# Omnetics.net
KiCad netlist of a schematic drawn in Altium Designer
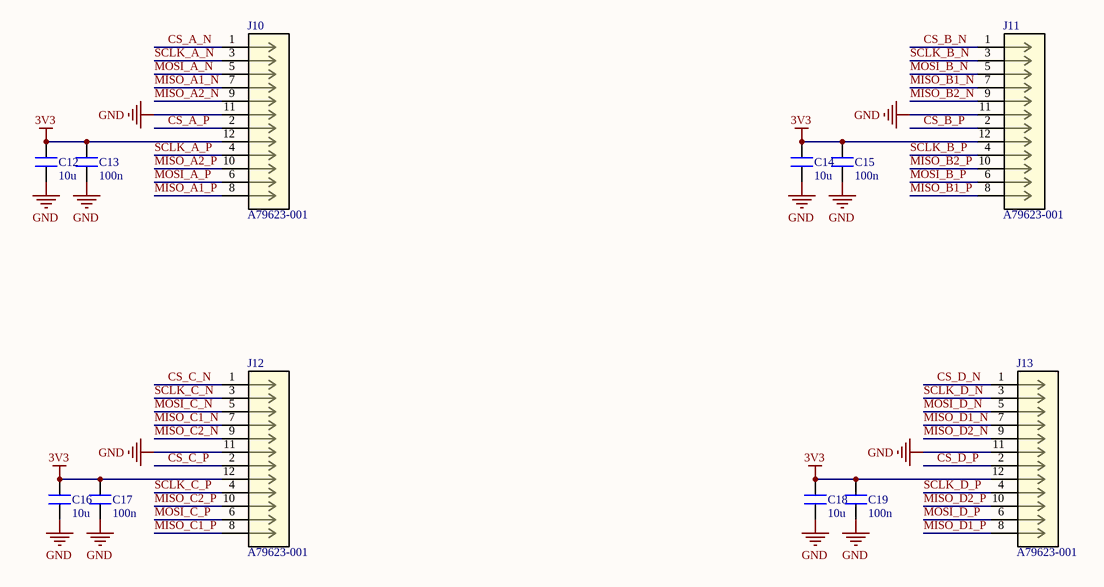
[diagram p0: Omnetics.SchDoc]

(export (version "E")
  (design (tool "Eeschema 10.0.6"))
  (components
    (comp (ref "C12") (value "10u") (footprint "C 0603_L") (libsource (lib "ZYNQ_开发板") (part "C_1_8")))
    (comp (ref "C13") (value "100n") (footprint "C 0402_L") (libsource (lib "ZYNQ_开发板") (part "C_1")))
    (comp (ref "C14") (value "10u") (footprint "C 0603_L") (libsource (lib "ZYNQ_开发板") (part "C_1_8")))
    (comp (ref "C15") (value "100n") (footprint "C 0402_L") (libsource (lib "ZYNQ_开发板") (part "C_1")))
    (comp (ref "C16") (value "10u") (footprint "C 0603_L") (libsource (lib "ZYNQ_开发板") (part "C_1_8")))
    (comp (ref "C17") (value "100n") (footprint "C 0402_L") (libsource (lib "ZYNQ_开发板") (part "C_1")))
    (comp (ref "C18") (value "10u") (footprint "C 0603_L") (libsource (lib "ZYNQ_开发板") (part "C_1_8")))
    (comp (ref "C19") (value "100n") (footprint "C 0402_L") (libsource (lib "ZYNQ_开发板") (part "C_1")))
    (comp (ref "J10")
      (value "A79623-001")
      (footprint "CONN_A79623-001_OMN")
      (description "Description")
      (fields (field (name "COPYRIGHT") "Copyright (C) 2026 Ultra Librarian. All rights reserved."))
      (libsource (lib "A79623-001") (part "A79623-001"))
    )
    (comp (ref "J11")
      (value "A79623-001")
      (footprint "CONN_A79623-001_OMN")
      (description "Description")
      (fields (field (name "COPYRIGHT") "Copyright (C) 2026 Ultra Librarian. All rights reserved."))
      (libsource (lib "A79623-001") (part "A79623-001"))
    )
    (comp (ref "J12")
      (value "A79623-001")
      (footprint "CONN_A79623-001_OMN")
      (description "Description")
      (fields (field (name "COPYRIGHT") "Copyright (C) 2026 Ultra Librarian. All rights reserved."))
      (libsource (lib "A79623-001") (part "A79623-001"))
    )
    (comp (ref "J13")
      (value "A79623-001")
      (footprint "CONN_A79623-001_OMN")
      (description "Description")
      (fields (field (name "COPYRIGHT") "Copyright (C) 2026 Ultra Librarian. All rights reserved."))
      (libsource (lib "A79623-001") (part "A79623-001"))
    )
  )
  (nets
    (net (code "1") (name "/CS_A_N") (class "Default")
      (node (ref "J10") (pin "1") (pinfunction "1_1") (pintype "passive"))
    )
    (net (code "2") (name "/CS_A_P") (class "Default")
      (node (ref "J10") (pin "2") (pinfunction "2_2") (pintype "passive"))
    )
    (net (code "3") (name "/CS_B_N") (class "Default")
      (node (ref "J11") (pin "1") (pinfunction "1_1") (pintype "passive"))
    )
    (net (code "4") (name "/CS_B_P") (class "Default")
      (node (ref "J11") (pin "2") (pinfunction "2_2") (pintype "passive"))
    )
    (net (code "5") (name "/CS_C_N") (class "Default")
      (node (ref "J12") (pin "1") (pinfunction "1_1") (pintype "passive"))
    )
    (net (code "6") (name "/CS_C_P") (class "Default")
      (node (ref "J12") (pin "2") (pinfunction "2_2") (pintype "passive"))
    )
    (net (code "7") (name "/CS_D_N") (class "Default")
      (node (ref "J13") (pin "1") (pinfunction "1_1") (pintype "passive"))
    )
    (net (code "8") (name "/CS_D_P") (class "Default")
      (node (ref "J13") (pin "2") (pinfunction "2_2") (pintype "passive"))
    )
    (net (code "9") (name "/MISO_A1_N") (class "Default")
      (node (ref "J10") (pin "7") (pinfunction "7_7") (pintype "passive"))
    )
    (net (code "10") (name "/MISO_A1_P") (class "Default")
      (node (ref "J10") (pin "8") (pinfunction "8_8") (pintype "passive"))
    )
    (net (code "11") (name "/MISO_A2_N") (class "Default")
      (node (ref "J10") (pin "9") (pinfunction "9_9") (pintype "passive"))
    )
    (net (code "12") (name "/MISO_A2_P") (class "Default")
      (node (ref "J10") (pin "10") (pinfunction "10_10") (pintype "passive"))
    )
    (net (code "13") (name "/MISO_B1_N") (class "Default")
      (node (ref "J11") (pin "7") (pinfunction "7_7") (pintype "passive"))
    )
    (net (code "14") (name "/MISO_B1_P") (class "Default")
      (node (ref "J11") (pin "8") (pinfunction "8_8") (pintype "passive"))
    )
    (net (code "15") (name "/MISO_B2_N") (class "Default")
      (node (ref "J11") (pin "9") (pinfunction "9_9") (pintype "passive"))
    )
    (net (code "16") (name "/MISO_B2_P") (class "Default")
      (node (ref "J11") (pin "10") (pinfunction "10_10") (pintype "passive"))
    )
    (net (code "17") (name "/MISO_C1_N") (class "Default")
      (node (ref "J12") (pin "7") (pinfunction "7_7") (pintype "passive"))
    )
    (net (code "18") (name "/MISO_C1_P") (class "Default")
      (node (ref "J12") (pin "8") (pinfunction "8_8") (pintype "passive"))
    )
    (net (code "19") (name "/MISO_C2_N") (class "Default")
      (node (ref "J12") (pin "9") (pinfunction "9_9") (pintype "passive"))
    )
    (net (code "20") (name "/MISO_C2_P") (class "Default")
      (node (ref "J12") (pin "10") (pinfunction "10_10") (pintype "passive"))
    )
    (net (code "21") (name "/MISO_D1_N") (class "Default")
      (node (ref "J13") (pin "7") (pinfunction "7_7") (pintype "passive"))
    )
    (net (code "22") (name "/MISO_D1_P") (class "Default")
      (node (ref "J13") (pin "8") (pinfunction "8_8") (pintype "passive"))
    )
    (net (code "23") (name "/MISO_D2_N") (class "Default")
      (node (ref "J13") (pin "9") (pinfunction "9_9") (pintype "passive"))
    )
    (net (code "24") (name "/MISO_D2_P") (class "Default")
      (node (ref "J13") (pin "10") (pinfunction "10_10") (pintype "passive"))
    )
    (net (code "25") (name "/MOSI_A_N") (class "Default")
      (node (ref "J10") (pin "5") (pinfunction "5_5") (pintype "passive"))
    )
    (net (code "26") (name "/MOSI_A_P") (class "Default")
      (node (ref "J10") (pin "6") (pinfunction "6_6") (pintype "passive"))
    )
    (net (code "27") (name "/MOSI_B_N") (class "Default")
      (node (ref "J11") (pin "5") (pinfunction "5_5") (pintype "passive"))
    )
    (net (code "28") (name "/MOSI_B_P") (class "Default")
      (node (ref "J11") (pin "6") (pinfunction "6_6") (pintype "passive"))
    )
    (net (code "29") (name "/MOSI_C_N") (class "Default")
      (node (ref "J12") (pin "5") (pinfunction "5_5") (pintype "passive"))
    )
    (net (code "30") (name "/MOSI_C_P") (class "Default")
      (node (ref "J12") (pin "6") (pinfunction "6_6") (pintype "passive"))
    )
    (net (code "31") (name "/MOSI_D_N") (class "Default")
      (node (ref "J13") (pin "5") (pinfunction "5_5") (pintype "passive"))
    )
    (net (code "32") (name "/MOSI_D_P") (class "Default")
      (node (ref "J13") (pin "6") (pinfunction "6_6") (pintype "passive"))
    )
    (net (code "33") (name "/SCLK_A_N") (class "Default")
      (node (ref "J10") (pin "3") (pinfunction "3_3") (pintype "passive"))
    )
    (net (code "34") (name "/SCLK_A_P") (class "Default")
      (node (ref "J10") (pin "4") (pinfunction "4_4") (pintype "passive"))
    )
    (net (code "35") (name "/SCLK_B_N") (class "Default")
      (node (ref "J11") (pin "3") (pinfunction "3_3") (pintype "passive"))
    )
    (net (code "36") (name "/SCLK_B_P") (class "Default")
      (node (ref "J11") (pin "4") (pinfunction "4_4") (pintype "passive"))
    )
    (net (code "37") (name "/SCLK_C_N") (class "Default")
      (node (ref "J12") (pin "3") (pinfunction "3_3") (pintype "passive"))
    )
    (net (code "38") (name "/SCLK_C_P") (class "Default")
      (node (ref "J12") (pin "4") (pinfunction "4_4") (pintype "passive"))
    )
    (net (code "39") (name "/SCLK_D_N") (class "Default")
      (node (ref "J13") (pin "3") (pinfunction "3_3") (pintype "passive"))
    )
    (net (code "40") (name "/SCLK_D_P") (class "Default")
      (node (ref "J13") (pin "4") (pinfunction "4_4") (pintype "passive"))
    )
    (net (code "41") (name "3V3") (class "Default")
      (node (ref "C12") (pin "2") (pintype "passive"))
      (node (ref "C13") (pin "2") (pintype "passive"))
      (node (ref "C14") (pin "2") (pintype "passive"))
      (node (ref "C15") (pin "2") (pintype "passive"))
      (node (ref "C16") (pin "2") (pintype "passive"))
      (node (ref "C17") (pin "2") (pintype "passive"))
      (node (ref "C18") (pin "2") (pintype "passive"))
      (node (ref "C19") (pin "2") (pintype "passive"))
      (node (ref "J10") (pin "12") (pinfunction "12_12") (pintype "passive"))
      (node (ref "J11") (pin "12") (pinfunction "12_12") (pintype "passive"))
      (node (ref "J12") (pin "12") (pinfunction "12_12") (pintype "passive"))
      (node (ref "J13") (pin "12") (pinfunction "12_12") (pintype "passive"))
    )
    (net (code "42") (name "GND") (class "Default")
      (node (ref "C12") (pin "1") (pintype "passive"))
      (node (ref "C13") (pin "1") (pintype "passive"))
      (node (ref "C14") (pin "1") (pintype "passive"))
      (node (ref "C15") (pin "1") (pintype "passive"))
      (node (ref "C16") (pin "1") (pintype "passive"))
      (node (ref "C17") (pin "1") (pintype "passive"))
      (node (ref "C18") (pin "1") (pintype "passive"))
      (node (ref "C19") (pin "1") (pintype "passive"))
      (node (ref "J10") (pin "11") (pinfunction "11_11") (pintype "passive"))
      (node (ref "J11") (pin "11") (pinfunction "11_11") (pintype "passive"))
      (node (ref "J12") (pin "11") (pinfunction "11_11") (pintype "passive"))
      (node (ref "J13") (pin "11") (pinfunction "11_11") (pintype "passive"))
    )
  )
)
